# PROC010B_LDO.net
KiCad netlist of a schematic drawn in Altium Designer
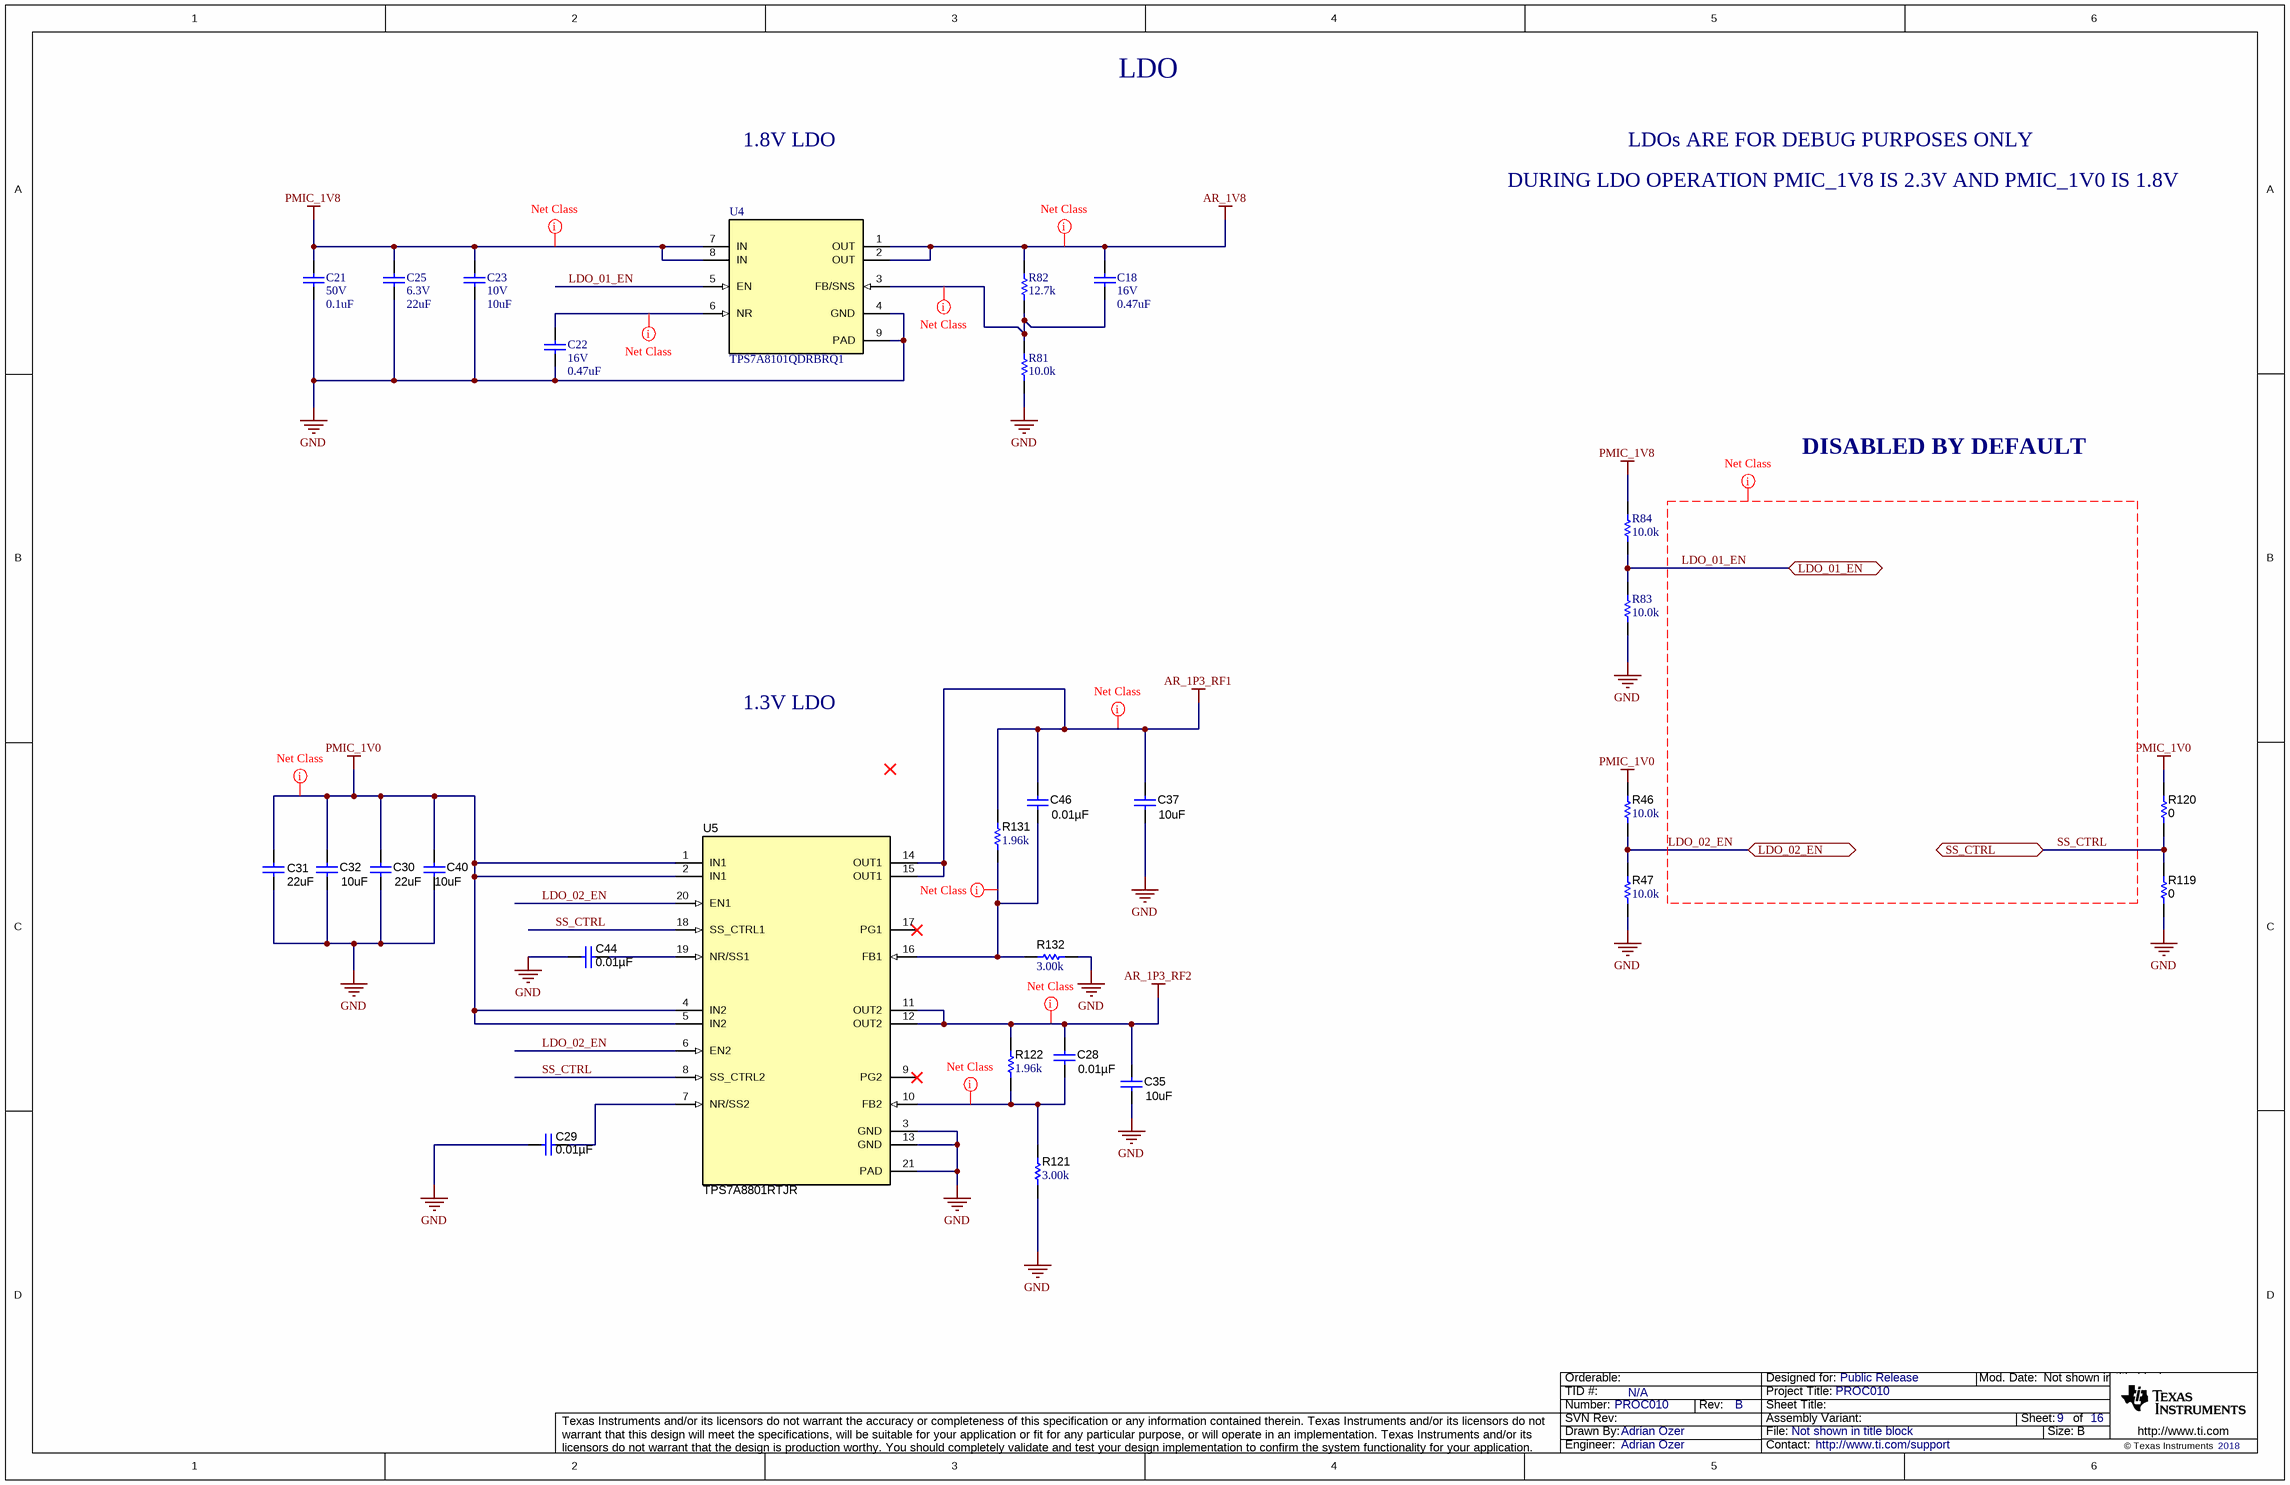
[diagram p0: PROC010B_LDO.SchDoc]

(export (version "E")
  (design (tool "Eeschema 10.0.6"))
  (components
    (comp (ref "C18")
      (value "GCM188R71C474KA55D")
      (footprint "0603")
      (description "CAP, CERM, 0.47 uF, 16 V, +/- 10%, X7R, AEC-Q200 Grade 1, 0603")
      (fields
        (field (name "MANUFACTURER") "MuRata")
        (field (name "VDC_V") "16V")
        (field (name "VALUEDISPLAYED") "0.47uF")
        (field (name "PUBLISHER") "Texas Instruments")
      )
      (libsource (lib "Altium Vault - TI") (part "Capacitor"))
    )
    (comp (ref "C21")
      (value "CGA2B3X7R1H104K050BB")
      (footprint "0402")
      (description "CAP, CERM, 0.1 uF, 50 V, +/- 10%, X7R, AEC-Q200 Grade 1, 0402")
      (fields
        (field (name "MANUFACTURER") "TDK")
        (field (name "VDC_V") "50V")
        (field (name "VALUEDISPLAYED") "0.1uF")
        (field (name "PUBLISHER") "Texas Instruments")
      )
      (libsource (lib "Altium Vault - TI") (part "Capacitor"))
    )
    (comp (ref "C22")
      (value "GCM188R71C474KA55D")
      (footprint "0603")
      (description "CAP, CERM, 0.47 uF, 16 V, +/- 10%, X7R, AEC-Q200 Grade 1, 0603")
      (fields
        (field (name "MANUFACTURER") "MuRata")
        (field (name "VDC_V") "16V")
        (field (name "VALUEDISPLAYED") "0.47uF")
        (field (name "PUBLISHER") "Texas Instruments")
      )
      (libsource (lib "Altium Vault - TI") (part "Capacitor"))
    )
    (comp (ref "C23")
      (value "GCM21BR71A106KE22L")
      (footprint "0805_HV")
      (description "CAP, CERM, 10 uF, 10 V, +/- 10%, X7R, 0805")
      (fields
        (field (name "MANUFACTURER") "MuRata")
        (field (name "VDC_V") "10V")
        (field (name "VALUEDISPLAYED") "10uF")
        (field (name "PUBLISHER") "Texas Instruments")
      )
      (libsource (lib "Altium Vault - TI") (part "Capacitor"))
    )
    (comp (ref "C25")
      (value "CGA5L1X7R0J226M160AC")
      (footprint "1206_180")
      (description "CAP, CERM, 22 uF, 6.3 V, +/- 10%, X7R, AEC-Q200 Grade 1, 1206")
      (fields
        (field (name "MANUFACTURER") "TDK")
        (field (name "VDC_V") "6.3V")
        (field (name "VALUEDISPLAYED") "22uF")
        (field (name "PUBLISHER") "Texas Instruments")
      )
      (libsource (lib "Altium Vault - TI") (part "Capacitor"))
    )
    (comp (ref "C28")
      (value "CGA2B3X8R1H103K050BB")
      (footprint "0402L")
      (description "CAP, CERM, 0.01 µF, 50 V,+/- 10%, X8R, AEC-Q200 Grade 0, 0402")
      (fields (field (name "MANUFACTURER") "TDK") (field (name "VALUEDISPLAYED") "0.01µF"))
      (libsource (lib "Altium Vault - TI") (part "Capacitor"))
    )
    (comp (ref "C29")
      (value "CGA2B3X8R1H103K050BB")
      (footprint "0402L")
      (description "CAP, CERM, 0.01 µF, 50 V,+/- 10%, X8R, AEC-Q200 Grade 0, 0402")
      (fields (field (name "MANUFACTURER") "TDK") (field (name "VALUEDISPLAYED") "0.01µF"))
      (libsource (lib "Altium Vault - TI") (part "Capacitor"))
    )
    (comp (ref "C30")
      (value "CGA5L1X7R0J226M160AC")
      (footprint "1206_180")
      (description "CAP, CERM, 22 uF, 6.3 V, +/- 10%, X7R, AEC-Q200 Grade 1, 1206")
      (fields
        (field (name "MANUFACTURER") "TDK")
        (field (name "VALUEDISPLAYED") "22uF")
        (field (name "PUBLISHER") "Texas Instruments")
      )
      (libsource (lib "Altium Vault - TI") (part "Capacitor"))
    )
    (comp (ref "C31")
      (value "CGA5L1X7R0J226M160AC")
      (footprint "1206_180")
      (description "CAP, CERM, 22 uF, 6.3 V, +/- 10%, X7R, AEC-Q200 Grade 1, 1206")
      (fields
        (field (name "MANUFACTURER") "TDK")
        (field (name "VALUEDISPLAYED") "22uF")
        (field (name "PUBLISHER") "Texas Instruments")
      )
      (libsource (lib "Altium Vault - TI") (part "Capacitor"))
    )
    (comp (ref "C32")
      (value "GCM21BR71A106KE22L")
      (footprint "0805")
      (description "CAP, CERM, 10 uF, 10 V, +/- 10%, X7R, 0805")
      (fields
        (field (name "MANUFACTURER") "MuRata")
        (field (name "VALUEDISPLAYED") "10uF")
        (field (name "PUBLISHER") "Texas Instruments")
      )
      (libsource (lib "Altium Vault - TI") (part "CMP-0008017-2"))
    )
    (comp (ref "C35")
      (value "GCM21BR71A106KE22L")
      (footprint "0805_HV")
      (description "CAP, CERM, 10 uF, 10 V, +/- 10%, X7R, 0805")
      (fields
        (field (name "MANUFACTURER") "MuRata")
        (field (name "VALUEDISPLAYED") "10uF")
        (field (name "PUBLISHER") "Texas Instruments")
      )
      (libsource (lib "Altium Vault - TI") (part "CMP-0008017-2"))
    )
    (comp (ref "C37")
      (value "GCM21BR71A106KE22L")
      (footprint "0805_HV")
      (description "CAP, CERM, 10 uF, 10 V, +/- 10%, X7R, 0805")
      (fields
        (field (name "MANUFACTURER") "MuRata")
        (field (name "VALUEDISPLAYED") "10uF")
        (field (name "PUBLISHER") "Texas Instruments")
      )
      (libsource (lib "Altium Vault - TI") (part "CMP-0008017-2"))
    )
    (comp (ref "C40")
      (value "GCM21BR71A106KE22L")
      (footprint "0805_HV1")
      (description "CAP, CERM, 10 uF, 10 V, +/- 10%, X7R, 0805")
      (fields
        (field (name "MANUFACTURER") "MuRata")
        (field (name "VALUEDISPLAYED") "10uF")
        (field (name "PUBLISHER") "Texas Instruments")
      )
      (libsource (lib "Altium Vault - TI") (part "CMP-0008017-2"))
    )
    (comp (ref "C44")
      (value "CGA2B3X8R1H103K050BB")
      (footprint "0402L")
      (description "CAP, CERM, 0.01 µF, 50 V,+/- 10%, X8R, AEC-Q200 Grade 0, 0402")
      (fields (field (name "MANUFACTURER") "TDK") (field (name "VALUEDISPLAYED") "0.01µF"))
      (libsource (lib "Altium Vault - TI") (part "Capacitor"))
    )
    (comp (ref "C46")
      (value "CGA2B3X8R1H103K050BB")
      (footprint "0402L")
      (description "CAP, CERM, 0.01 µF, 50 V,+/- 10%, X8R, AEC-Q200 Grade 0, 0402")
      (fields (field (name "MANUFACTURER") "TDK") (field (name "VALUEDISPLAYED") "0.01µF"))
      (libsource (lib "Altium Vault - TI") (part "Capacitor"))
    )
    (comp (ref "R46")
      (value "CRCW040210K0FKED")
      (footprint "0402L")
      (description "RES, 10.0 k, 1%, 0.063 W, AEC-Q200 Grade 0, 0402")
      (fields (field (name "MANUFACTURER") "Vishay-Dale") (field (name "VALUEDISPLAYED") "10.0k"))
      (libsource (lib "Altium Vault - TI") (part "Resistor"))
    )
    (comp (ref "R47")
      (value "CRCW040210K0FKED")
      (footprint "0402L")
      (description "RES, 10.0 k, 1%, 0.063 W, AEC-Q200 Grade 0, 0402")
      (fields (field (name "MANUFACTURER") "Vishay-Dale") (field (name "VALUEDISPLAYED") "10.0k"))
      (libsource (lib "Altium Vault - TI") (part "Resistor"))
    )
    (comp (ref "R81")
      (value "CRCW040210K0FKED")
      (footprint "0402L")
      (description "RES, 10.0 k, 1%, 0.063 W, AEC-Q200 Grade 0, 0402")
      (fields (field (name "MANUFACTURER") "Vishay-Dale") (field (name "VALUEDISPLAYED") "10.0k"))
      (libsource (lib "Altium Vault - TI") (part "CMP-0025958-3"))
    )
    (comp (ref "R82")
      (value "CRCW040212K7FKED")
      (footprint "0402L")
      (description "RES, 12.7 k, 1%, 0.063 W, AEC-Q200 Grade 0, 0402")
      (fields (field (name "MANUFACTURER") "Vishay-Dale") (field (name "VALUEDISPLAYED") "12.7k"))
      (libsource (lib "Altium Vault - TI") (part "CMP-0025993-3"))
    )
    (comp (ref "R83")
      (value "CRCW040210K0FKED")
      (footprint "0402")
      (description "RES, 10.0 k, 1%, 0.063 W, AEC-Q200 Grade 0, 0402")
      (fields (field (name "MANUFACTURER") "Vishay-Dale") (field (name "VALUEDISPLAYED") "10.0k"))
      (libsource (lib "Altium Vault - TI") (part "Resistor"))
    )
    (comp (ref "R84")
      (value "CRCW040210K0FKED")
      (footprint "0402")
      (description "RES, 10.0 k, 1%, 0.063 W, AEC-Q200 Grade 0, 0402")
      (fields (field (name "MANUFACTURER") "Vishay-Dale") (field (name "VALUEDISPLAYED") "10.0k"))
      (libsource (lib "Altium Vault - TI") (part "Resistor"))
    )
    (comp (ref "R119")
      (value "ERJ-2GE0R00X")
      (footprint "0402L")
      (description "RES, 0, 5%, 0.063 W, 0402")
      (fields
        (field (name "MANUFACTURER") "Panasonic")
        (field (name "VALUEDISPLAYED") "0")
        (field (name "PUBLISHER") "Texas Instruments")
      )
      (libsource (lib "Altium Vault - TI") (part "Resistor"))
    )
    (comp (ref "R120")
      (value "ERJ-2GE0R00X")
      (footprint "0402L")
      (description "RES, 0, 5%, 0.063 W, 0402")
      (fields
        (field (name "MANUFACTURER") "Panasonic")
        (field (name "VALUEDISPLAYED") "0")
        (field (name "PUBLISHER") "Texas Instruments")
      )
      (libsource (lib "Altium Vault - TI") (part "CMP-0026992-2"))
    )
    (comp (ref "R121")
      (value "CRCW04023K00FKED")
      (footprint "0402L")
      (description "RES, 3.00 k, 1%, 0.063 W, AEC-Q200 Grade 0, 0402")
      (fields (field (name "MANUFACTURER") "Vishay-Dale") (field (name "VALUEDISPLAYED") "3.00k"))
      (libsource (lib "Altium Vault - TI") (part "Resistor"))
    )
    (comp (ref "R122")
      (value "CRCW04021K96FKED")
      (footprint "0402L")
      (description "RES, 1.96 k, 1%, 0.063 W, AEC-Q200 Grade 0, 0402")
      (fields (field (name "MANUFACTURER") "Vishay-Dale") (field (name "VALUEDISPLAYED") "1.96k"))
      (libsource (lib "Altium Vault - TI") (part "Resistor"))
    )
    (comp (ref "R131")
      (value "CRCW04021K96FKED")
      (footprint "0402L")
      (description "RES, 1.96 k, 1%, 0.063 W, AEC-Q200 Grade 0, 0402")
      (fields (field (name "MANUFACTURER") "Vishay-Dale") (field (name "VALUEDISPLAYED") "1.96k"))
      (libsource (lib "Altium Vault - TI") (part "Resistor"))
    )
    (comp (ref "R132")
      (value "CRCW04023K00FKED")
      (footprint "0402L")
      (description "RES, 3.00 k, 1%, 0.063 W, AEC-Q200 Grade 0, 0402")
      (fields (field (name "MANUFACTURER") "Vishay-Dale") (field (name "VALUEDISPLAYED") "3.00k"))
      (libsource (lib "Altium Vault - TI") (part "Resistor"))
    )
    (comp (ref "U4")
      (value "TPS7A8101QDRBRQ1")
      (footprint "DRB0008A")
      (fields
        (field (name "MANUFACTURER") "Texas Instruments")
        (field (name "PARTNUMBER") "TPS7A8101QDRBRQ1")
        (field (name "PUBLISHER") "Texas Instruments")
      )
      (libsource (lib "Altium Vault - TI") (part "TPS7A80xx"))
    )
    (comp (ref "U5")
      (value "TPS7A8801RTJR")
      (footprint "RTJ0020D")
      (description "Dual, 1-A, Low Noise (3.8-uVRMS), LDO Voltage Regulator, RTJ0020D (WQFN-20)")
      (fields
        (field (name "ALTERNATE PARTNUMBER") "TPS7A8801RTJT")
        (field (name "MANUFACTURER") "Texas Instruments")
        (field (name "PARTNUMBER") "TPS7A8801RTJR")
        (field (name "PUBLISHER") "Texas Instruments")
      )
      (libsource (lib "Altium Vault - TI") (part "TPS7A8801"))
    )
  )
  (nets
    (net (code "1") (name "/LDO_01_EN") (class "Default")
      (node (ref "R83") (pin "2") (pinfunction "2_2") (pintype "passive"))
      (node (ref "R84") (pin "1") (pinfunction "1_1") (pintype "passive"))
      (node (ref "U4") (pin "5") (pinfunction "EN_5") (pintype "input"))
    )
    (net (code "2") (name "/LDO_02_EN") (class "Default")
      (node (ref "R46") (pin "2") (pinfunction "2_2") (pintype "passive"))
      (node (ref "R47") (pin "1") (pinfunction "1_1") (pintype "passive"))
      (node (ref "U5") (pin "20") (pinfunction "EN1_20") (pintype "input"))
      (node (ref "U5") (pin "6") (pinfunction "EN2_6") (pintype "input"))
    )
    (net (code "3") (name "/SS_CTRL") (class "Default")
      (node (ref "R119") (pin "2") (pinfunction "2_2") (pintype "passive"))
      (node (ref "R120") (pin "1") (pinfunction "1_1") (pintype "passive"))
      (node (ref "U5") (pin "18") (pinfunction "SS_CTRL1_18") (pintype "input"))
      (node (ref "U5") (pin "8") (pinfunction "SS_CTRL2_8") (pintype "input"))
    )
    (net (code "4") (name "AR_1P3_RF1") (class "Default")
      (node (ref "C37") (pin "2") (pinfunction "2_2") (pintype "passive"))
      (node (ref "C46") (pin "2") (pinfunction "2_2") (pintype "passive"))
      (node (ref "R131") (pin "2") (pinfunction "2_2") (pintype "passive"))
      (node (ref "U5") (pin "14") (pinfunction "OUT1_14") (pintype "power_in"))
      (node (ref "U5") (pin "15") (pinfunction "OUT1_15") (pintype "power_in"))
    )
    (net (code "5") (name "AR_1P3_RF2") (class "Default")
      (node (ref "C28") (pin "2") (pinfunction "2_2") (pintype "passive"))
      (node (ref "C35") (pin "2") (pinfunction "2_2") (pintype "passive"))
      (node (ref "R122") (pin "2") (pinfunction "2_2") (pintype "passive"))
      (node (ref "U5") (pin "11") (pinfunction "OUT2_11") (pintype "power_in"))
      (node (ref "U5") (pin "12") (pinfunction "OUT2_12") (pintype "power_in"))
    )
    (net (code "6") (name "AR_1V8") (class "Default")
      (node (ref "C18") (pin "1") (pinfunction "1_1") (pintype "passive"))
      (node (ref "R82") (pin "2") (pinfunction "2_2") (pintype "passive"))
      (node (ref "U4") (pin "1") (pinfunction "OUT_1") (pintype "power_in"))
      (node (ref "U4") (pin "2") (pinfunction "OUT_2") (pintype "power_in"))
    )
    (net (code "7") (name "GND") (class "Default")
      (node (ref "C21") (pin "2") (pinfunction "2_2") (pintype "passive"))
      (node (ref "C22") (pin "2") (pinfunction "2_2") (pintype "passive"))
      (node (ref "C23") (pin "2") (pinfunction "2_2") (pintype "passive"))
      (node (ref "C25") (pin "2") (pinfunction "2_2") (pintype "passive"))
      (node (ref "C29") (pin "1") (pinfunction "1_1") (pintype "passive"))
      (node (ref "C30") (pin "1") (pinfunction "1_1") (pintype "passive"))
      (node (ref "C31") (pin "1") (pinfunction "1_1") (pintype "passive"))
      (node (ref "C32") (pin "1") (pinfunction "1_1") (pintype "passive"))
      (node (ref "C35") (pin "1") (pinfunction "1_1") (pintype "passive"))
      (node (ref "C37") (pin "1") (pinfunction "1_1") (pintype "passive"))
      (node (ref "C40") (pin "1") (pinfunction "1_1") (pintype "passive"))
      (node (ref "C44") (pin "1") (pinfunction "1_1") (pintype "passive"))
      (node (ref "R119") (pin "1") (pinfunction "1_1") (pintype "passive"))
      (node (ref "R121") (pin "1") (pinfunction "1_1") (pintype "passive"))
      (node (ref "R132") (pin "1") (pinfunction "1_1") (pintype "passive"))
      (node (ref "R47") (pin "2") (pinfunction "2_2") (pintype "passive"))
      (node (ref "R81") (pin "1") (pinfunction "1_1") (pintype "passive"))
      (node (ref "R83") (pin "1") (pinfunction "1_1") (pintype "passive"))
      (node (ref "U4") (pin "4") (pinfunction "GND_4") (pintype "power_in"))
      (node (ref "U4") (pin "9") (pinfunction "PAD_9") (pintype "passive"))
      (node (ref "U5") (pin "13") (pinfunction "GND_13") (pintype "power_in"))
      (node (ref "U5") (pin "21") (pinfunction "PAD_21") (pintype "power_in"))
      (node (ref "U5") (pin "3") (pinfunction "GND_3") (pintype "power_in"))
    )
    (net (code "8") (name "Net-(U4-FB{slash}SNS)") (class "Default")
      (node (ref "C18") (pin "2") (pinfunction "2_2") (pintype "passive"))
      (node (ref "R81") (pin "2") (pinfunction "2_2") (pintype "passive"))
      (node (ref "R82") (pin "1") (pinfunction "1_1") (pintype "passive"))
      (node (ref "U4") (pin "3") (pinfunction "FB/SNS_3") (pintype "input"))
    )
    (net (code "9") (name "Net-(U4-NR)") (class "Default")
      (node (ref "C22") (pin "1") (pinfunction "1_1") (pintype "passive"))
      (node (ref "U4") (pin "6") (pinfunction "NR_6") (pintype "input"))
    )
    (net (code "10") (name "Net-(U5-FB1)") (class "Default")
      (node (ref "C46") (pin "1") (pinfunction "1_1") (pintype "passive"))
      (node (ref "R131") (pin "1") (pinfunction "1_1") (pintype "passive"))
      (node (ref "R132") (pin "2") (pinfunction "2_2") (pintype "passive"))
      (node (ref "U5") (pin "16") (pinfunction "FB1_16") (pintype "input"))
    )
    (net (code "11") (name "Net-(U5-FB2)") (class "Default")
      (node (ref "C28") (pin "1") (pinfunction "1_1") (pintype "passive"))
      (node (ref "R121") (pin "2") (pinfunction "2_2") (pintype "passive"))
      (node (ref "R122") (pin "1") (pinfunction "1_1") (pintype "passive"))
      (node (ref "U5") (pin "10") (pinfunction "FB2_10") (pintype "input"))
    )
    (net (code "12") (name "Net-(U5-NR{slash}SS1)") (class "Default")
      (node (ref "C44") (pin "2") (pinfunction "2_2") (pintype "passive"))
      (node (ref "U5") (pin "19") (pinfunction "NR/SS1_19") (pintype "input"))
    )
    (net (code "13") (name "Net-(U5-NR{slash}SS2)") (class "Default")
      (node (ref "C29") (pin "2") (pinfunction "2_2") (pintype "passive"))
      (node (ref "U5") (pin "7") (pinfunction "NR/SS2_7") (pintype "input"))
    )
    (net (code "14") (name "PMIC_1V0") (class "Default")
      (node (ref "C30") (pin "2") (pinfunction "2_2") (pintype "passive"))
      (node (ref "C31") (pin "2") (pinfunction "2_2") (pintype "passive"))
      (node (ref "C32") (pin "2") (pinfunction "2_2") (pintype "passive"))
      (node (ref "C40") (pin "2") (pinfunction "2_2") (pintype "passive"))
      (node (ref "R120") (pin "2") (pinfunction "2_2") (pintype "passive"))
      (node (ref "R46") (pin "1") (pinfunction "1_1") (pintype "passive"))
      (node (ref "U5") (pin "1") (pinfunction "IN1_1") (pintype "power_in"))
      (node (ref "U5") (pin "2") (pinfunction "IN1_2") (pintype "power_in"))
      (node (ref "U5") (pin "4") (pinfunction "IN2_4") (pintype "power_in"))
      (node (ref "U5") (pin "5") (pinfunction "IN2_5") (pintype "power_in"))
    )
    (net (code "15") (name "PMIC_1V8") (class "Default")
      (node (ref "C21") (pin "1") (pinfunction "1_1") (pintype "passive"))
      (node (ref "C23") (pin "1") (pinfunction "1_1") (pintype "passive"))
      (node (ref "C25") (pin "1") (pinfunction "1_1") (pintype "passive"))
      (node (ref "R84") (pin "2") (pinfunction "2_2") (pintype "passive"))
      (node (ref "U4") (pin "7") (pinfunction "IN_7") (pintype "power_in"))
      (node (ref "U4") (pin "8") (pinfunction "IN_8") (pintype "power_in"))
    )
    (net (code "16") (name "unconnected-(U5-PG1-Pad17)") (class "Default")
      (node (ref "U5") (pin "17") (pinfunction "PG1_17") (pintype "open_collector+no_connect"))
    )
    (net (code "17") (name "unconnected-(U5-PG2-Pad9)") (class "Default")
      (node (ref "U5") (pin "9") (pinfunction "PG2_9") (pintype "open_collector+no_connect"))
    )
  )
)
